# v3_2.net
KiCad netlist of a schematic drawn in EAGLE
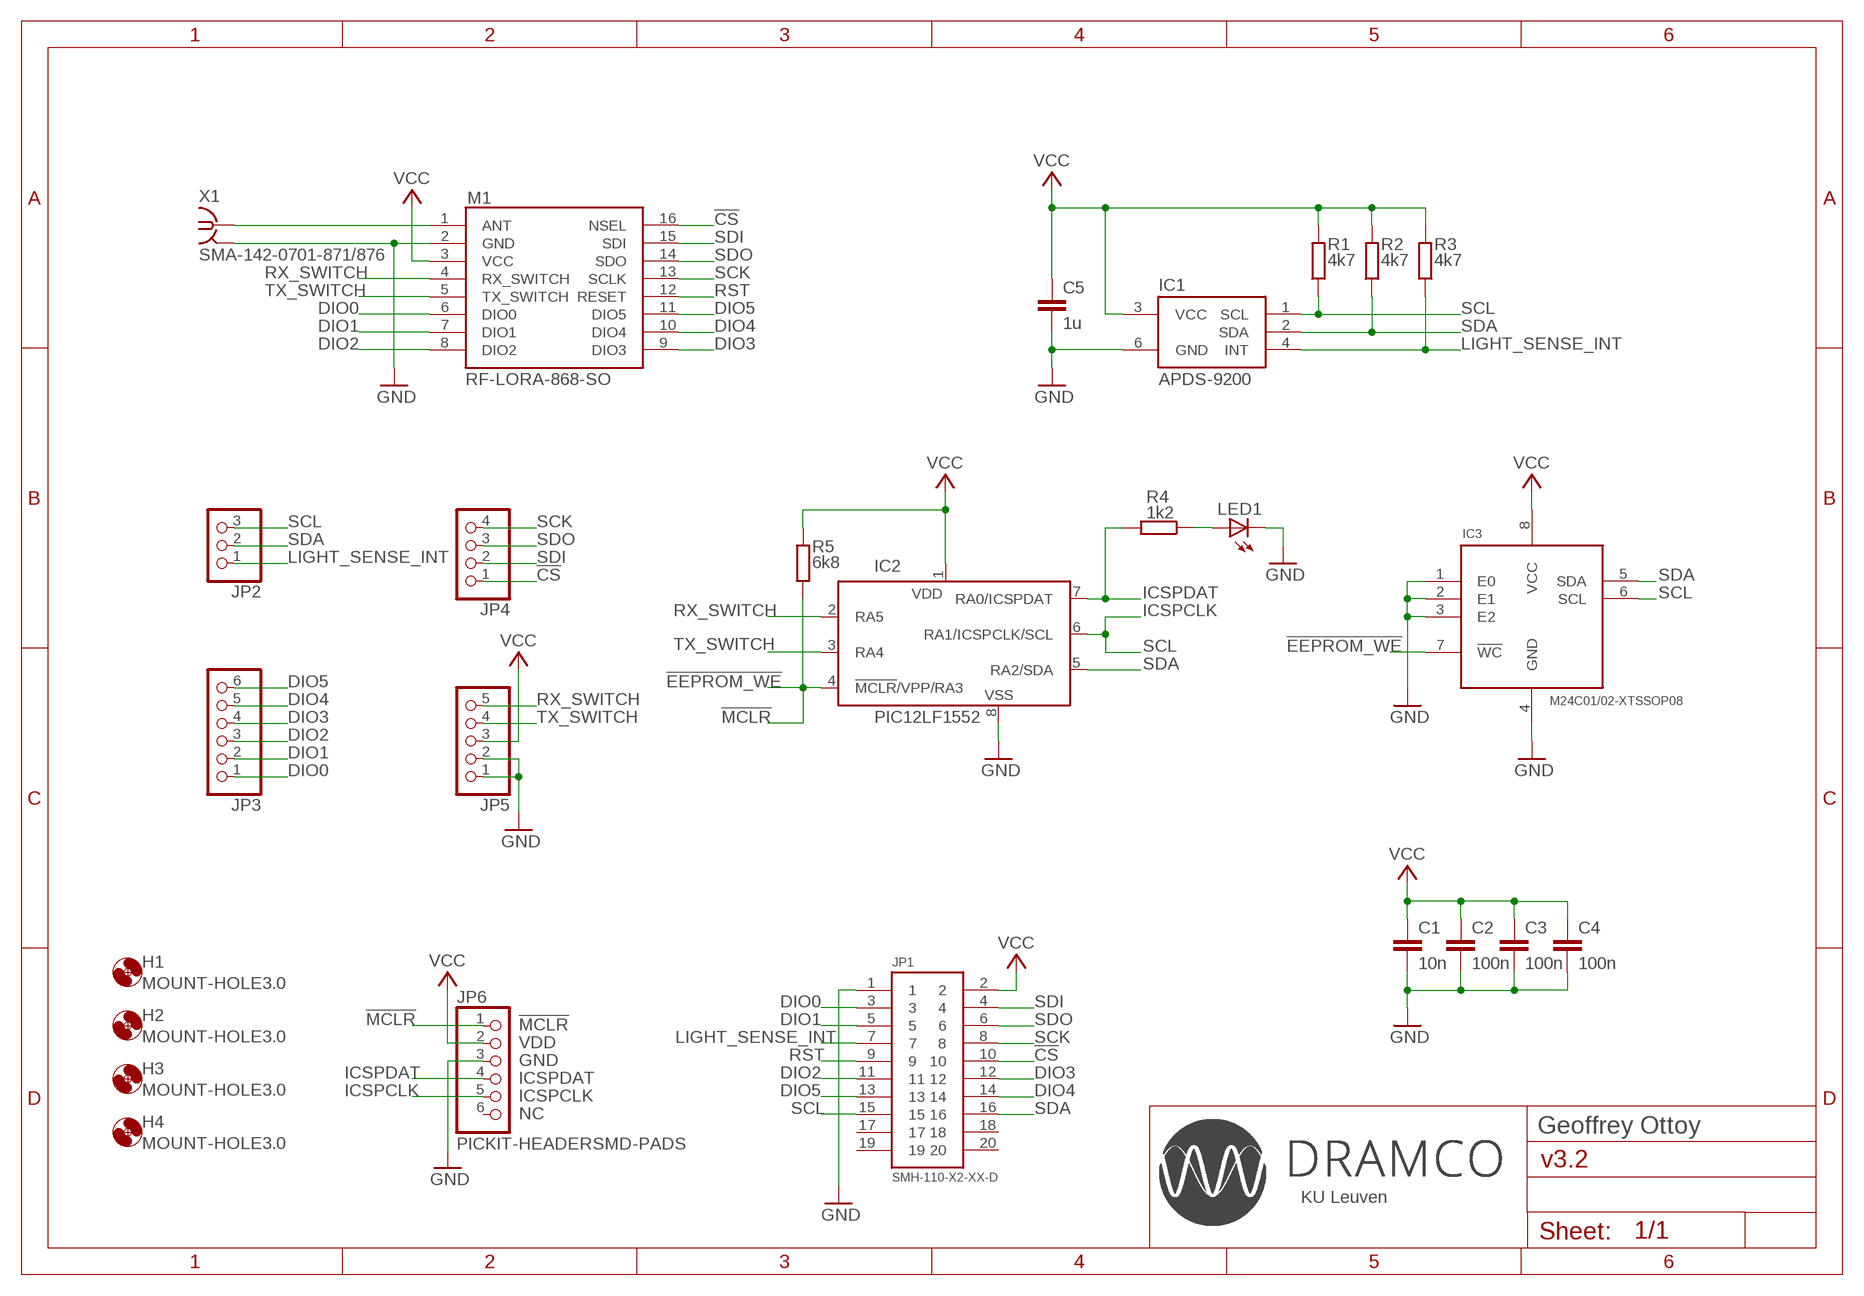
[diagram p0: schematic, sheet 1]

(export (version "E")
  (design (tool "Eeschema 10.0.6"))
  (components
    (comp (ref "C1")
      (value "10n")
      (footprint "eagle-import:C0805K")
      (libsource (lib "eagle-import") (part "C-EUC0805K"))
    )
    (comp (ref "C2")
      (value "100n")
      (footprint "eagle-import:C0805K")
      (libsource (lib "eagle-import") (part "C-EUC0805K"))
    )
    (comp (ref "C3")
      (value "100n")
      (footprint "eagle-import:C0805K")
      (libsource (lib "eagle-import") (part "C-EUC0805K"))
    )
    (comp (ref "C4")
      (value "100n")
      (footprint "eagle-import:C0805K")
      (libsource (lib "eagle-import") (part "C-EUC0805K"))
    )
    (comp (ref "C5")
      (value "1u")
      (footprint "eagle-import:C0805K")
      (libsource (lib "eagle-import") (part "C-EUC0805K"))
    )
    (comp (ref "H1")
      (value "MOUNT-HOLE3.0")
      (footprint "eagle-import:3,0")
      (libsource (lib "eagle-import") (part "MOUNT-HOLE3.0"))
    )
    (comp (ref "H2")
      (value "MOUNT-HOLE3.0")
      (footprint "eagle-import:3,0")
      (libsource (lib "eagle-import") (part "MOUNT-HOLE3.0"))
    )
    (comp (ref "H3")
      (value "MOUNT-HOLE3.0")
      (footprint "eagle-import:3,0")
      (libsource (lib "eagle-import") (part "MOUNT-HOLE3.0"))
    )
    (comp (ref "H4")
      (value "MOUNT-HOLE3.0")
      (footprint "eagle-import:3,0")
      (libsource (lib "eagle-import") (part "MOUNT-HOLE3.0"))
    )
    (comp (ref "IC1")
      (value "APDS-9200")
      (footprint "eagle-import:APDS-9200")
      (libsource (lib "eagle-import") (part "APDS-9200"))
    )
    (comp (ref "IC2")
      (value "PIC12LF1552")
      (footprint "eagle-import:MSOP8")
      (libsource (lib "eagle-import") (part "PIC12LF1552"))
    )
    (comp (ref "IC3")
      (value "M24C01/02-XTSSOP08")
      (footprint "eagle-import:TSSOP08")
      (libsource (lib "eagle-import") (part "M24C01/02-XTSSOP08"))
    )
    (comp (ref "JP1")
      (value "SMH-110-X2-XX-D")
      (footprint "eagle-import:SMH-110-X2-XX-D")
      (libsource (lib "eagle-import") (part "SMH-110-X2-XX-D"))
    )
    (comp (ref "JP2")
      (value "PINHD-1X3")
      (footprint "eagle-import:1X03")
      (libsource (lib "eagle-import") (part "PINHD-1X3"))
    )
    (comp (ref "JP3")
      (value "PINHD-1X6")
      (footprint "eagle-import:1X06")
      (libsource (lib "eagle-import") (part "PINHD-1X6"))
    )
    (comp (ref "JP4")
      (value "PINHD-1X4")
      (footprint "eagle-import:1X04")
      (libsource (lib "eagle-import") (part "PINHD-1X4"))
    )
    (comp (ref "JP5")
      (value "PINHD-1X5")
      (footprint "eagle-import:1X05")
      (libsource (lib "eagle-import") (part "PINHD-1X5"))
    )
    (comp (ref "JP6")
      (value "PICKIT-HEADERSMD-PADS")
      (footprint "eagle-import:1X06_SMD")
      (libsource (lib "eagle-import") (part "PICKIT-HEADERSMD-PADS"))
    )
    (comp (ref "LED1")
      (value "LEDCHIP-LED0805")
      (footprint "eagle-import:CHIP-LED0805")
      (libsource (lib "eagle-import") (part "LEDCHIP-LED0805"))
    )
    (comp (ref "M1")
      (value "RF-LORA-868-SO")
      (footprint "eagle-import:RF-LORA-868-SO")
      (libsource (lib "eagle-import") (part "RF-LORA-868-SO"))
    )
    (comp (ref "R1")
      (value "4k7")
      (footprint "eagle-import:M0805")
      (libsource (lib "eagle-import") (part "R-EU_M0805"))
    )
    (comp (ref "R2")
      (value "4k7")
      (footprint "eagle-import:M0805")
      (libsource (lib "eagle-import") (part "R-EU_M0805"))
    )
    (comp (ref "R3")
      (value "4k7")
      (footprint "eagle-import:M0805")
      (libsource (lib "eagle-import") (part "R-EU_M0805"))
    )
    (comp (ref "R4")
      (value "1k2")
      (footprint "eagle-import:M0805")
      (libsource (lib "eagle-import") (part "R-EU_M0805"))
    )
    (comp (ref "R5")
      (value "6k8")
      (footprint "eagle-import:M0805")
      (libsource (lib "eagle-import") (part "R-EU_M0805"))
    )
    (comp (ref "X1")
      (value "SMA-142-0701-871/876")
      (footprint "eagle-import:J502-ND-142-0701-871_876")
      (fields (field (name "MF") "JOHNSON COMPONENTS") (field (name "MPN") "142-0701-871"))
      (libsource (lib "eagle-import") (part "SMA-142-0701-871/876"))
    )
  )
  (nets
    (net (code "1") (name "/DIO0") (class "Default")
      (node (ref "JP1") (pin "3") (pinfunction "3_3") (pintype "bidirectional"))
      (node (ref "JP3") (pin "1") (pinfunction "1_1") (pintype "passive"))
      (node (ref "M1") (pin "6") (pinfunction "DIO0_6") (pintype "bidirectional"))
    )
    (net (code "2") (name "/DIO1") (class "Default")
      (node (ref "JP1") (pin "5") (pinfunction "5_5") (pintype "bidirectional"))
      (node (ref "JP3") (pin "2") (pinfunction "2_2") (pintype "passive"))
      (node (ref "M1") (pin "7") (pinfunction "DIO1_7") (pintype "bidirectional"))
    )
    (net (code "3") (name "/DIO2") (class "Default")
      (node (ref "JP1") (pin "11") (pinfunction "11_11") (pintype "bidirectional"))
      (node (ref "JP3") (pin "3") (pinfunction "3_3") (pintype "passive"))
      (node (ref "M1") (pin "8") (pinfunction "DIO2_8") (pintype "bidirectional"))
    )
    (net (code "4") (name "/DIO3") (class "Default")
      (node (ref "JP1") (pin "12") (pinfunction "12_12") (pintype "bidirectional"))
      (node (ref "JP3") (pin "4") (pinfunction "4_4") (pintype "passive"))
      (node (ref "M1") (pin "9") (pinfunction "DIO3_9") (pintype "bidirectional"))
    )
    (net (code "5") (name "/DIO4") (class "Default")
      (node (ref "JP1") (pin "14") (pinfunction "14_14") (pintype "bidirectional"))
      (node (ref "JP3") (pin "5") (pinfunction "5_5") (pintype "passive"))
      (node (ref "M1") (pin "10") (pinfunction "DIO4_10") (pintype "bidirectional"))
    )
    (net (code "6") (name "/DIO5") (class "Default")
      (node (ref "JP1") (pin "13") (pinfunction "13_13") (pintype "bidirectional"))
      (node (ref "JP3") (pin "6") (pinfunction "6_6") (pintype "passive"))
      (node (ref "M1") (pin "11") (pinfunction "DIO5_11") (pintype "bidirectional"))
    )
    (net (code "7") (name "/ICSPDAT") (class "Default")
      (node (ref "IC2") (pin "7") (pinfunction "RA0/ICSPDAT_7") (pintype "bidirectional"))
      (node (ref "JP6") (pin "4") (pinfunction "4_4") (pintype "passive"))
      (node (ref "R4") (pin "2") (pinfunction "2_2") (pintype "passive"))
    )
    (net (code "8") (name "/LIGHT_SENSE_INT") (class "Default")
      (node (ref "IC1") (pin "4") (pinfunction "INT_4") (pintype "bidirectional"))
      (node (ref "JP1") (pin "7") (pinfunction "7_7") (pintype "bidirectional"))
      (node (ref "JP2") (pin "1") (pinfunction "1_1") (pintype "passive"))
      (node (ref "R3") (pin "1") (pinfunction "1_1") (pintype "passive"))
    )
    (net (code "9") (name "/RST") (class "Default")
      (node (ref "JP1") (pin "9") (pinfunction "9_9") (pintype "bidirectional"))
      (node (ref "M1") (pin "12") (pinfunction "RESET_12") (pintype "bidirectional"))
    )
    (net (code "10") (name "/RX_SWITCH") (class "Default")
      (node (ref "IC2") (pin "2") (pinfunction "RA5_2") (pintype "bidirectional"))
      (node (ref "JP5") (pin "5") (pinfunction "5_5") (pintype "passive"))
      (node (ref "M1") (pin "4") (pinfunction "RX_SWITCH_4") (pintype "bidirectional"))
    )
    (net (code "11") (name "/SCK") (class "Default")
      (node (ref "JP1") (pin "8") (pinfunction "8_8") (pintype "bidirectional"))
      (node (ref "JP4") (pin "4") (pinfunction "4_4") (pintype "passive"))
      (node (ref "M1") (pin "13") (pinfunction "SCLK_13") (pintype "bidirectional"))
    )
    (net (code "12") (name "/SCL") (class "Default")
      (node (ref "IC1") (pin "1") (pinfunction "SCL_1") (pintype "bidirectional"))
      (node (ref "IC2") (pin "6") (pinfunction "RA1/ICSPCLK/SCL_6") (pintype "bidirectional"))
      (node (ref "IC3") (pin "6") (pinfunction "SCL_6") (pintype "bidirectional"))
      (node (ref "JP1") (pin "15") (pinfunction "15_15") (pintype "bidirectional"))
      (node (ref "JP2") (pin "3") (pinfunction "3_3") (pintype "passive"))
      (node (ref "JP6") (pin "5") (pinfunction "5_5") (pintype "passive"))
      (node (ref "R1") (pin "1") (pinfunction "1_1") (pintype "passive"))
    )
    (net (code "13") (name "/SDA") (class "Default")
      (node (ref "IC1") (pin "2") (pinfunction "SDA_2") (pintype "bidirectional"))
      (node (ref "IC2") (pin "5") (pinfunction "RA2/SDA_5") (pintype "bidirectional"))
      (node (ref "IC3") (pin "5") (pinfunction "SDA_5") (pintype "bidirectional"))
      (node (ref "JP1") (pin "16") (pinfunction "16_16") (pintype "bidirectional"))
      (node (ref "JP2") (pin "2") (pinfunction "2_2") (pintype "passive"))
      (node (ref "R2") (pin "1") (pinfunction "1_1") (pintype "passive"))
    )
    (net (code "14") (name "/SDI") (class "Default")
      (node (ref "JP1") (pin "4") (pinfunction "4_4") (pintype "bidirectional"))
      (node (ref "JP4") (pin "2") (pinfunction "2_2") (pintype "passive"))
      (node (ref "M1") (pin "15") (pinfunction "SDI_15") (pintype "bidirectional"))
    )
    (net (code "15") (name "/SDO") (class "Default")
      (node (ref "JP1") (pin "6") (pinfunction "6_6") (pintype "bidirectional"))
      (node (ref "JP4") (pin "3") (pinfunction "3_3") (pintype "passive"))
      (node (ref "M1") (pin "14") (pinfunction "SDO_14") (pintype "bidirectional"))
    )
    (net (code "16") (name "/TX_SWITCH") (class "Default")
      (node (ref "IC2") (pin "3") (pinfunction "RA4_3") (pintype "bidirectional"))
      (node (ref "JP5") (pin "4") (pinfunction "4_4") (pintype "passive"))
      (node (ref "M1") (pin "5") (pinfunction "TX_SWITCH_5") (pintype "bidirectional"))
    )
    (net (code "17") (name "/~{CS}") (class "Default")
      (node (ref "JP1") (pin "10") (pinfunction "10_10") (pintype "bidirectional"))
      (node (ref "JP4") (pin "1") (pinfunction "1_1") (pintype "passive"))
      (node (ref "M1") (pin "16") (pinfunction "NSEL_16") (pintype "bidirectional"))
    )
    (net (code "18") (name "/~{MCLR}") (class "Default")
      (node (ref "IC2") (pin "4") (pinfunction "~{MCLR}/VPP/RA3_4") (pintype "input"))
      (node (ref "IC3") (pin "7") (pinfunction "~{WC}_7") (pintype "bidirectional"))
      (node (ref "JP6") (pin "1") (pinfunction "1_1") (pintype "passive"))
      (node (ref "R5") (pin "1") (pinfunction "1_1") (pintype "passive"))
    )
    (net (code "19") (name "GND") (class "Default")
      (node (ref "C1") (pin "2") (pinfunction "2_2") (pintype "passive"))
      (node (ref "C2") (pin "2") (pinfunction "2_2") (pintype "passive"))
      (node (ref "C3") (pin "2") (pinfunction "2_2") (pintype "passive"))
      (node (ref "C4") (pin "2") (pinfunction "2_2") (pintype "passive"))
      (node (ref "C5") (pin "2") (pinfunction "2_2") (pintype "passive"))
      (node (ref "IC1") (pin "6") (pinfunction "GND_6") (pintype "bidirectional"))
      (node (ref "IC2") (pin "8") (pinfunction "VSS_8") (pintype "power_in"))
      (node (ref "IC3") (pin "1") (pinfunction "E0_1") (pintype "bidirectional"))
      (node (ref "IC3") (pin "2") (pinfunction "E1_2") (pintype "bidirectional"))
      (node (ref "IC3") (pin "3") (pinfunction "E2_3") (pintype "bidirectional"))
      (node (ref "IC3") (pin "4") (pinfunction "GND_4") (pintype "bidirectional"))
      (node (ref "JP1") (pin "1") (pinfunction "1_1") (pintype "bidirectional"))
      (node (ref "JP5") (pin "1") (pinfunction "1_1") (pintype "passive"))
      (node (ref "JP5") (pin "2") (pinfunction "2_2") (pintype "passive"))
      (node (ref "JP6") (pin "3") (pinfunction "3_3") (pintype "passive"))
      (node (ref "LED1") (pin "C") (pinfunction "C_C") (pintype "passive"))
      (node (ref "M1") (pin "2") (pinfunction "GND_2") (pintype "bidirectional"))
      (node (ref "X1") (pin "G@1") (pinfunction "2_G@1") (pintype "passive"))
      (node (ref "X1") (pin "G@2") (pinfunction "2_G@2") (pintype "passive"))
      (node (ref "X1") (pin "G@3") (pinfunction "2_G@3") (pintype "passive"))
      (node (ref "X1") (pin "G@4") (pinfunction "2_G@4") (pintype "passive"))
    )
    (net (code "20") (name "Net-(LED1-PadA)") (class "Default")
      (node (ref "LED1") (pin "A") (pinfunction "A_A") (pintype "passive"))
      (node (ref "R4") (pin "1") (pinfunction "1_1") (pintype "passive"))
    )
    (net (code "21") (name "Net-(M1-ANT)") (class "Default")
      (node (ref "M1") (pin "1") (pinfunction "ANT_1") (pintype "bidirectional"))
      (node (ref "X1") (pin "1") (pinfunction "1_1") (pintype "passive"))
    )
    (net (code "22") (name "VCC") (class "Default")
      (node (ref "C1") (pin "1") (pinfunction "1_1") (pintype "passive"))
      (node (ref "C2") (pin "1") (pinfunction "1_1") (pintype "passive"))
      (node (ref "C3") (pin "1") (pinfunction "1_1") (pintype "passive"))
      (node (ref "C4") (pin "1") (pinfunction "1_1") (pintype "passive"))
      (node (ref "C5") (pin "1") (pinfunction "1_1") (pintype "passive"))
      (node (ref "IC1") (pin "3") (pinfunction "VCC_3") (pintype "bidirectional"))
      (node (ref "IC2") (pin "1") (pinfunction "VDD_1") (pintype "power_in"))
      (node (ref "IC3") (pin "8") (pinfunction "VCC_8") (pintype "bidirectional"))
      (node (ref "JP1") (pin "2") (pinfunction "2_2") (pintype "bidirectional"))
      (node (ref "JP5") (pin "3") (pinfunction "3_3") (pintype "passive"))
      (node (ref "JP6") (pin "2") (pinfunction "2_2") (pintype "passive"))
      (node (ref "M1") (pin "3") (pinfunction "VCC_3") (pintype "bidirectional"))
      (node (ref "R1") (pin "2") (pinfunction "2_2") (pintype "passive"))
      (node (ref "R2") (pin "2") (pinfunction "2_2") (pintype "passive"))
      (node (ref "R3") (pin "2") (pinfunction "2_2") (pintype "passive"))
      (node (ref "R5") (pin "2") (pinfunction "2_2") (pintype "passive"))
    )
    (net (code "23") (name "unconnected-(JP1-Pad17)") (class "Default")
      (node (ref "JP1") (pin "17") (pinfunction "17_17") (pintype "bidirectional"))
    )
    (net (code "24") (name "unconnected-(JP1-Pad18)") (class "Default")
      (node (ref "JP1") (pin "18") (pinfunction "18_18") (pintype "bidirectional"))
    )
    (net (code "25") (name "unconnected-(JP1-Pad19)") (class "Default")
      (node (ref "JP1") (pin "19") (pinfunction "19_19") (pintype "bidirectional"))
    )
    (net (code "26") (name "unconnected-(JP1-Pad20)") (class "Default")
      (node (ref "JP1") (pin "20") (pinfunction "20_20") (pintype "bidirectional"))
    )
    (net (code "27") (name "unconnected-(JP6-Pad6)") (class "Default")
      (node (ref "JP6") (pin "6") (pinfunction "6_6") (pintype "passive"))
    )
  )
)
